# design.net
KiCad netlist of a schematic drawn in Altium Designer
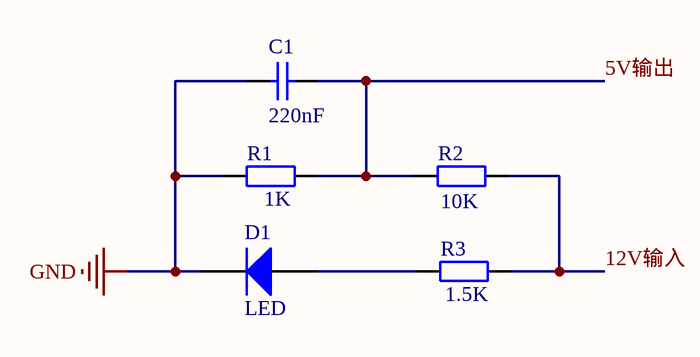
[diagram p0: 电压检测模块.SchDoc]

(export (version "E")
  (design (tool "Eeschema 10.0.6"))
  (components
    (comp (ref "C1")
      (value "220nF")
      (footprint "RAD-0.3")
      (description "Capacitor")
      (fields (field (name "Comment") "Cap") (field (name "PUBLISHER") "Altium Limited"))
      (libsource (lib "Miscellaneous Devices") (part "Cap"))
    )
    (comp (ref "D1")
      (value "LED")
      (footprint "SMC")
      (description "Default Diode")
      (fields (field (name "PUBLISHER") "Altium Limited"))
      (libsource (lib "Miscellaneous Devices") (part "Diode"))
    )
    (comp (ref "R1")
      (value "1K")
      (footprint "AXIAL-0.4")
      (description "Resistor")
      (fields (field (name "Comment") "Res2") (field (name "PUBLISHER") "Altium Limited"))
      (libsource (lib "Miscellaneous Devices") (part "Res2"))
    )
    (comp (ref "R2")
      (value "10K")
      (footprint "AXIAL-0.4")
      (description "Resistor")
      (fields (field (name "Comment") "Res2") (field (name "PUBLISHER") "Altium Limited"))
      (libsource (lib "Miscellaneous Devices") (part "Res2"))
    )
    (comp (ref "R3")
      (value "1.5K")
      (footprint "AXIAL-0.4")
      (description "Resistor")
      (fields (field (name "Comment") "Res2") (field (name "PUBLISHER") "Altium Limited"))
      (libsource (lib "Miscellaneous Devices") (part "Res2"))
    )
  )
  (nets
    (net (code "1") (name "/5V输出") (class "Default")
      (node (ref "C1") (pin "2") (pinfunction "2_2") (pintype "passive"))
      (node (ref "R1") (pin "2") (pinfunction "2_2") (pintype "passive"))
      (node (ref "R2") (pin "1") (pinfunction "1_1") (pintype "passive"))
    )
    (net (code "2") (name "/12V输入") (class "Default")
      (node (ref "R2") (pin "2") (pinfunction "2_2") (pintype "passive"))
      (node (ref "R3") (pin "2") (pinfunction "2_2") (pintype "passive"))
    )
    (net (code "3") (name "GND") (class "Default")
      (node (ref "C1") (pin "1") (pinfunction "1_1") (pintype "passive"))
      (node (ref "D1") (pin "2") (pinfunction "K_2") (pintype "passive"))
      (node (ref "R1") (pin "1") (pinfunction "1_1") (pintype "passive"))
    )
    (net (code "4") (name "Net-(D1-A)") (class "Default")
      (node (ref "D1") (pin "1") (pinfunction "A_1") (pintype "passive"))
      (node (ref "R3") (pin "1") (pinfunction "1_1") (pintype "passive"))
    )
  )
)
